# power_breakout.net
KiCad netlist of a schematic drawn in EAGLE
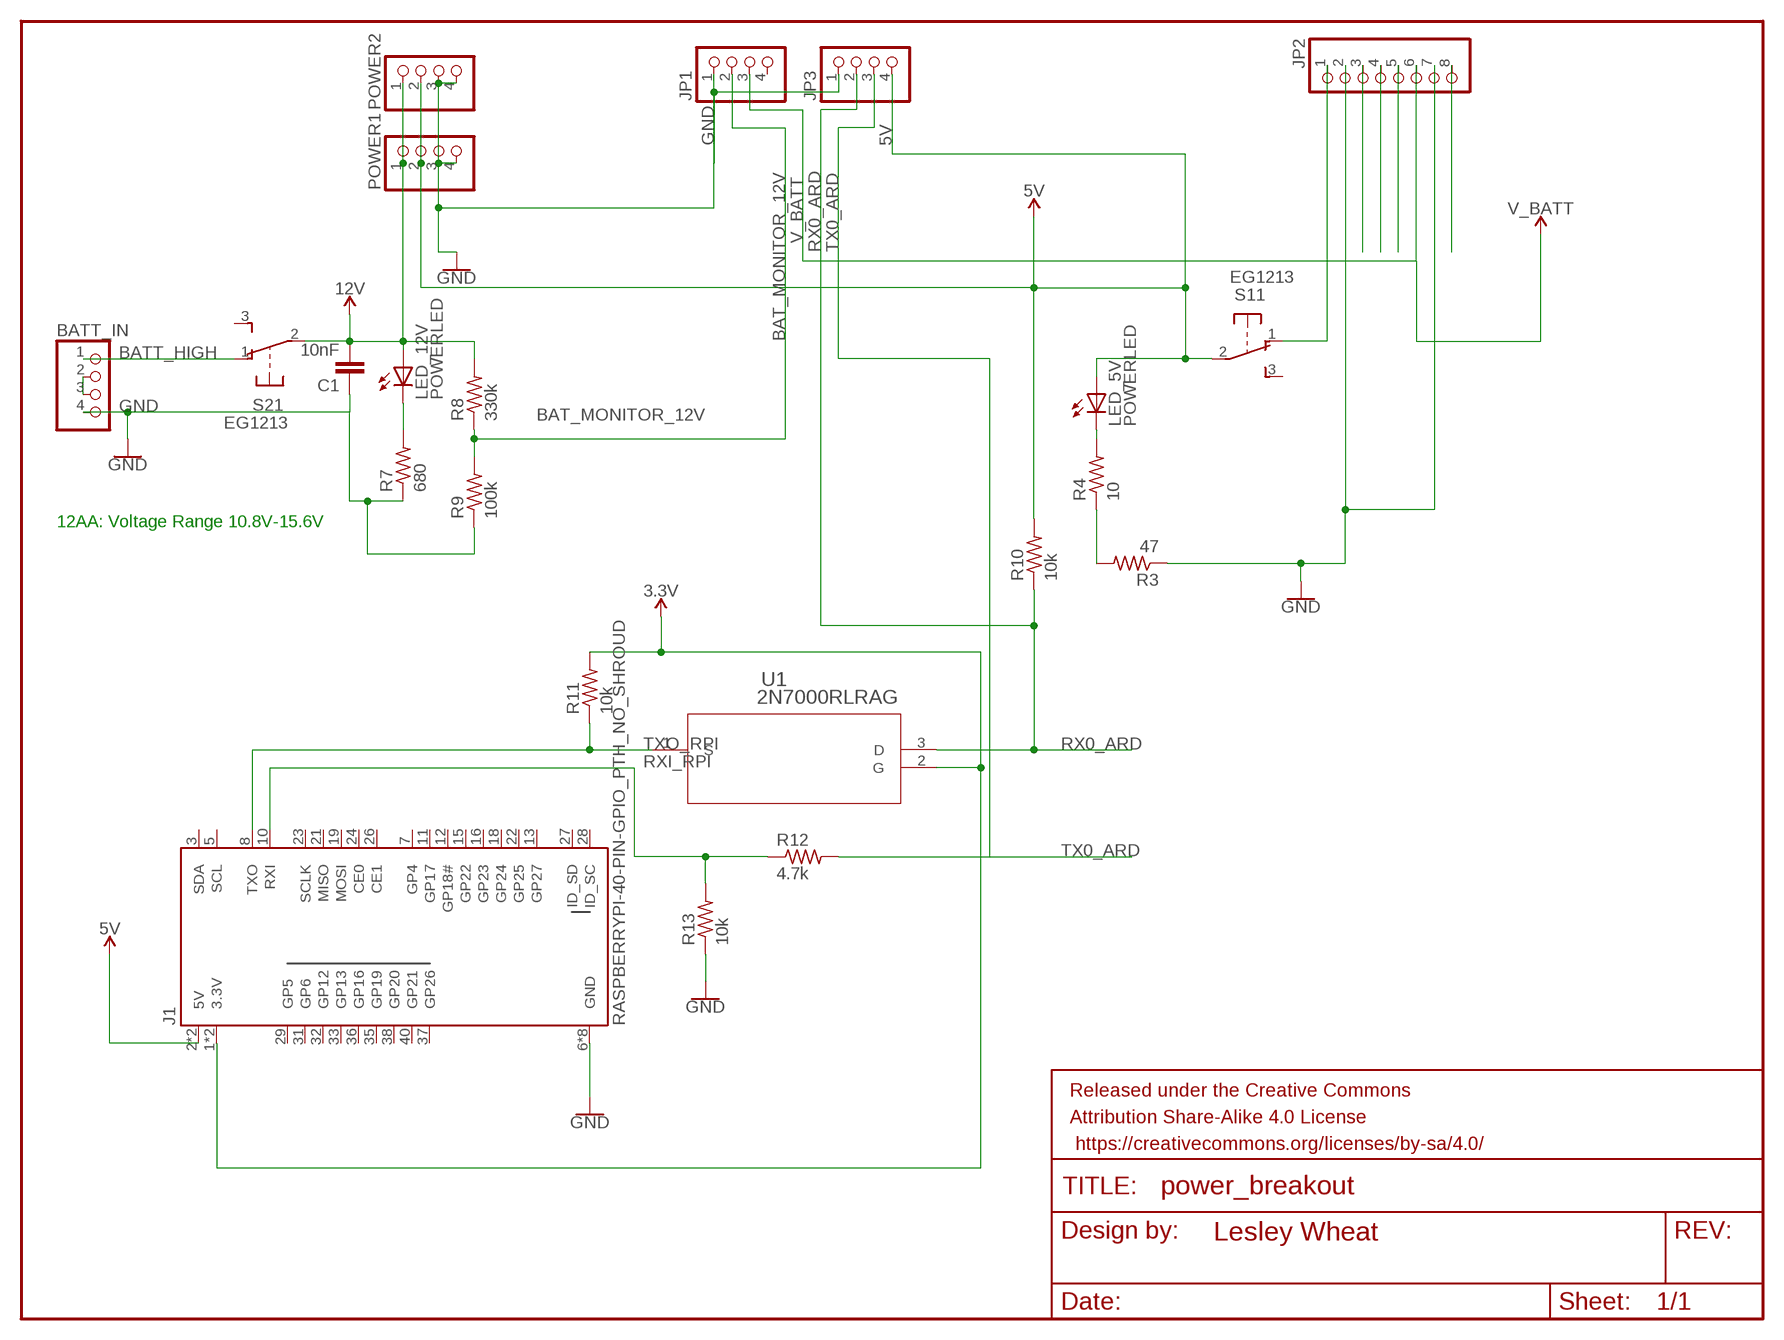
[diagram p0: schematic, sheet 1]

(export (version "E")
  (design (tool "Eeschema 10.0.6"))
  (components
    (comp (ref "BATT_IN")
      (value "PINHD-1X4")
      (footprint "eagle-import:1X04")
      (libsource (lib "eagle-import") (part "PINHD-1X4"))
    )
    (comp (ref "C1")
      (value "10nF")
      (footprint "eagle-import:CAP-PTH-10MM")
      (libsource (lib "eagle-import") (part "10NF-PTH-10MM-10000V-1-%"))
    )
    (comp (ref "FRAME1")
      (value "FRAME-LETTERNO_PACKAGE")
      (footprint "eagle-import:DUMMY")
      (fields (field (name "DESIGNER") "Lesley Wheat") (field (name "DESIGNER_1") "Lesley Wheat"))
      (libsource (lib "eagle-import") (part "FRAME-LETTERNO_PACKAGE"))
    )
    (comp (ref "J1")
      (value "RASPBERRYPI-40-PIN-GPIO_PTH_NO_SHROUD")
      (footprint "eagle-import:2X20")
      (libsource (lib "eagle-import") (part "RASPBERRYPI-40-PIN-GPIO_PTH_NO_SHROUD"))
    )
    (comp (ref "JP1")
      (value "PINHD-1X4")
      (footprint "eagle-import:1X04")
      (libsource (lib "eagle-import") (part "PINHD-1X4"))
    )
    (comp (ref "JP2")
      (value "PINHD-1X8")
      (footprint "eagle-import:1X08")
      (libsource (lib "eagle-import") (part "PINHD-1X8"))
    )
    (comp (ref "JP3")
      (value "PINHD-1X4")
      (footprint "eagle-import:1X04")
      (libsource (lib "eagle-import") (part "PINHD-1X4"))
    )
    (comp (ref "LED_5V")
      (value "POWERLED")
      (footprint "eagle-import:LED5MM")
      (libsource (lib "eagle-import") (part "LED5MM"))
    )
    (comp (ref "LED_12V")
      (value "POWERLED")
      (footprint "eagle-import:LED5MM")
      (libsource (lib "eagle-import") (part "LED5MM"))
    )
    (comp (ref "POWER1")
      (value "PINHD-1X4")
      (footprint "eagle-import:1X04")
      (libsource (lib "eagle-import") (part "PINHD-1X4"))
    )
    (comp (ref "POWER2")
      (value "PINHD-1X4")
      (footprint "eagle-import:1X04")
      (libsource (lib "eagle-import") (part "PINHD-1X4"))
    )
    (comp (ref "R3")
      (value "47")
      (footprint "eagle-import:0207_12")
      (libsource (lib "eagle-import") (part "R-US_0207/12"))
    )
    (comp (ref "R4")
      (value "10")
      (footprint "eagle-import:0207_12")
      (libsource (lib "eagle-import") (part "R-US_0207/12"))
    )
    (comp (ref "R7")
      (value "680")
      (footprint "eagle-import:0207_12")
      (libsource (lib "eagle-import") (part "R-US_0207/12"))
    )
    (comp (ref "R8")
      (value "330k")
      (footprint "eagle-import:0207_12")
      (libsource (lib "eagle-import") (part "R-US_0207/12"))
    )
    (comp (ref "R9")
      (value "100k")
      (footprint "eagle-import:0207_12")
      (libsource (lib "eagle-import") (part "R-US_0207/12"))
    )
    (comp (ref "R10")
      (value "10k")
      (footprint "eagle-import:0207_12")
      (libsource (lib "eagle-import") (part "R-US_0207/12"))
    )
    (comp (ref "R11")
      (value "10k")
      (footprint "eagle-import:0207_12")
      (libsource (lib "eagle-import") (part "R-US_0207/12"))
    )
    (comp (ref "R12")
      (value "4.7k")
      (footprint "eagle-import:0207_12")
      (libsource (lib "eagle-import") (part "R-US_0207/12"))
    )
    (comp (ref "R13")
      (value "10k")
      (footprint "eagle-import:0207_12")
      (libsource (lib "eagle-import") (part "R-US_0207/12"))
    )
    (comp (ref "S1")
      (value "EG1213")
      (footprint "eagle-import:EG1213")
      (libsource (lib "eagle-import") (part "EG1213"))
    )
    (comp (ref "S2")
      (value "EG1213")
      (footprint "eagle-import:EG1213")
      (libsource (lib "eagle-import") (part "EG1213"))
    )
    (comp (ref "U1")
      (value "2N7000RLRAG")
      (footprint "eagle-import:TO-92")
      (libsource (lib "eagle-import") (part "2N7000RLRAG"))
    )
  )
  (nets
    (net (code "1") (name "/BATT_HIGH") (class "Default")
      (node (ref "BATT_IN") (pin "1") (pinfunction "1_1") (pintype "passive"))
      (node (ref "S2") (pin "1") (pinfunction "O_1") (pintype "passive"))
    )
    (net (code "2") (name "/BAT_MONITOR_12V") (class "Default")
      (node (ref "JP1") (pin "2") (pinfunction "2_2") (pintype "passive"))
      (node (ref "R8") (pin "1") (pinfunction "1_1") (pintype "passive"))
      (node (ref "R9") (pin "2") (pinfunction "2_2") (pintype "passive"))
    )
    (net (code "3") (name "/RX0_ARD") (class "Default")
      (node (ref "JP3") (pin "2") (pinfunction "2_2") (pintype "passive"))
      (node (ref "R10") (pin "1") (pinfunction "1_1") (pintype "passive"))
      (node (ref "U1") (pin "3") (pinfunction "D_3") (pintype "passive"))
    )
    (net (code "4") (name "/RXI_RPI") (class "Default")
      (node (ref "J1") (pin "10") (pinfunction "RXI_10") (pintype "input"))
      (node (ref "R12") (pin "1") (pinfunction "1_1") (pintype "passive"))
      (node (ref "R13") (pin "2") (pinfunction "2_2") (pintype "passive"))
    )
    (net (code "5") (name "/TX0_ARD") (class "Default")
      (node (ref "JP3") (pin "3") (pinfunction "3_3") (pintype "passive"))
      (node (ref "R12") (pin "2") (pinfunction "2_2") (pintype "passive"))
    )
    (net (code "6") (name "/TXO_RPI") (class "Default")
      (node (ref "J1") (pin "8") (pinfunction "TXO_8") (pintype "output"))
      (node (ref "R11") (pin "1") (pinfunction "1_1") (pintype "passive"))
      (node (ref "U1") (pin "1") (pinfunction "S_1") (pintype "passive"))
    )
    (net (code "7") (name "3.3V") (class "Default")
      (node (ref "J1") (pin "1") (pinfunction "3.3V_1") (pintype "power_in"))
      (node (ref "J1") (pin "17") (pinfunction "3.3V_17") (pintype "power_in"))
      (node (ref "R11") (pin "2") (pinfunction "2_2") (pintype "passive"))
      (node (ref "U1") (pin "2") (pinfunction "G_2") (pintype "passive"))
    )
    (net (code "8") (name "5V") (class "Default")
      (node (ref "J1") (pin "2") (pinfunction "5V_2") (pintype "power_in"))
      (node (ref "J1") (pin "4") (pinfunction "5V_4") (pintype "power_in"))
      (node (ref "JP3") (pin "4") (pinfunction "4_4") (pintype "passive"))
      (node (ref "LED_5V") (pin "A") (pinfunction "A_A") (pintype "passive"))
      (node (ref "POWER1") (pin "2") (pinfunction "2_2") (pintype "passive"))
      (node (ref "POWER2") (pin "2") (pinfunction "2_2") (pintype "passive"))
      (node (ref "R10") (pin "2") (pinfunction "2_2") (pintype "passive"))
      (node (ref "S1") (pin "2") (pinfunction "P_2") (pintype "passive"))
    )
    (net (code "9") (name "12V") (class "Default")
      (node (ref "C1") (pin "2") (pinfunction "2_2") (pintype "passive"))
      (node (ref "LED_12V") (pin "A") (pinfunction "A_A") (pintype "passive"))
      (node (ref "POWER1") (pin "1") (pinfunction "1_1") (pintype "passive"))
      (node (ref "POWER2") (pin "1") (pinfunction "1_1") (pintype "passive"))
      (node (ref "R8") (pin "2") (pinfunction "2_2") (pintype "passive"))
      (node (ref "S2") (pin "2") (pinfunction "P_2") (pintype "passive"))
    )
    (net (code "10") (name "GND") (class "Default")
      (node (ref "BATT_IN") (pin "4") (pinfunction "4_4") (pintype "passive"))
      (node (ref "C1") (pin "1") (pinfunction "1_1") (pintype "passive"))
      (node (ref "J1") (pin "14") (pinfunction "GND_14") (pintype "power_in"))
      (node (ref "J1") (pin "20") (pinfunction "GND_20") (pintype "power_in"))
      (node (ref "J1") (pin "25") (pinfunction "GND_25") (pintype "power_in"))
      (node (ref "J1") (pin "30") (pinfunction "GND_30") (pintype "power_in"))
      (node (ref "J1") (pin "34") (pinfunction "GND_34") (pintype "power_in"))
      (node (ref "J1") (pin "39") (pinfunction "GND_39") (pintype "power_in"))
      (node (ref "J1") (pin "6") (pinfunction "GND_6") (pintype "power_in"))
      (node (ref "J1") (pin "9") (pinfunction "GND_9") (pintype "power_in"))
      (node (ref "JP1") (pin "1") (pinfunction "1_1") (pintype "passive"))
      (node (ref "JP2") (pin "2") (pinfunction "2_2") (pintype "passive"))
      (node (ref "JP2") (pin "7") (pinfunction "7_7") (pintype "passive"))
      (node (ref "JP3") (pin "1") (pinfunction "1_1") (pintype "passive"))
      (node (ref "POWER1") (pin "3") (pinfunction "3_3") (pintype "passive"))
      (node (ref "POWER1") (pin "4") (pinfunction "4_4") (pintype "passive"))
      (node (ref "POWER2") (pin "3") (pinfunction "3_3") (pintype "passive"))
      (node (ref "POWER2") (pin "4") (pinfunction "4_4") (pintype "passive"))
      (node (ref "R13") (pin "1") (pinfunction "1_1") (pintype "passive"))
      (node (ref "R3") (pin "1") (pinfunction "1_1") (pintype "passive"))
      (node (ref "R7") (pin "1") (pinfunction "1_1") (pintype "passive"))
      (node (ref "R9") (pin "1") (pinfunction "1_1") (pintype "passive"))
    )
    (net (code "11") (name "Net-(BATT_IN-Pad2)") (class "Default")
      (node (ref "BATT_IN") (pin "2") (pinfunction "2_2") (pintype "passive"))
      (node (ref "BATT_IN") (pin "3") (pinfunction "3_3") (pintype "passive"))
    )
    (net (code "12") (name "Net-(LED_5V-C)") (class "Default")
      (node (ref "LED_5V") (pin "K") (pinfunction "C_K") (pintype "passive"))
      (node (ref "R4") (pin "2") (pinfunction "2_2") (pintype "passive"))
    )
    (net (code "13") (name "Net-(LED_12V-C)") (class "Default")
      (node (ref "LED_12V") (pin "K") (pinfunction "C_K") (pintype "passive"))
      (node (ref "R7") (pin "2") (pinfunction "2_2") (pintype "passive"))
    )
    (net (code "14") (name "Net-(R3-Pad2)") (class "Default")
      (node (ref "R3") (pin "2") (pinfunction "2_2") (pintype "passive"))
      (node (ref "R4") (pin "1") (pinfunction "1_1") (pintype "passive"))
    )
    (net (code "15") (name "Net-(S1A-O)") (class "Default")
      (node (ref "JP2") (pin "1") (pinfunction "1_1") (pintype "passive"))
      (node (ref "S1") (pin "1") (pinfunction "O_1") (pintype "passive"))
    )
    (net (code "16") (name "V_BATT") (class "Default")
      (node (ref "JP1") (pin "3") (pinfunction "3_3") (pintype "passive"))
      (node (ref "JP2") (pin "6") (pinfunction "6_6") (pintype "passive"))
    )
    (net (code "17") (name "unconnected-(J1-CE0-Pad24)") (class "Default")
      (node (ref "J1") (pin "24") (pinfunction "CE0_24") (pintype "output"))
    )
    (net (code "18") (name "unconnected-(J1-CE1-Pad26)") (class "Default")
      (node (ref "J1") (pin "26") (pinfunction "CE1_26") (pintype "output"))
    )
    (net (code "19") (name "unconnected-(J1-GP4-Pad7)") (class "Default")
      (node (ref "J1") (pin "7") (pinfunction "GP4_7") (pintype "bidirectional"))
    )
    (net (code "20") (name "unconnected-(J1-GP5-Pad29)") (class "Default")
      (node (ref "J1") (pin "29") (pinfunction "GP5_29") (pintype "bidirectional"))
    )
    (net (code "21") (name "unconnected-(J1-GP6-Pad31)") (class "Default")
      (node (ref "J1") (pin "31") (pinfunction "GP6_31") (pintype "bidirectional"))
    )
    (net (code "22") (name "unconnected-(J1-GP12-Pad32)") (class "Default")
      (node (ref "J1") (pin "32") (pinfunction "GP12_32") (pintype "bidirectional"))
    )
    (net (code "23") (name "unconnected-(J1-GP13-Pad33)") (class "Default")
      (node (ref "J1") (pin "33") (pinfunction "GP13_33") (pintype "bidirectional"))
    )
    (net (code "24") (name "unconnected-(J1-GP16-Pad36)") (class "Default")
      (node (ref "J1") (pin "36") (pinfunction "GP16_36") (pintype "bidirectional"))
    )
    (net (code "25") (name "unconnected-(J1-GP17-Pad11)") (class "Default")
      (node (ref "J1") (pin "11") (pinfunction "GP17_11") (pintype "bidirectional"))
    )
    (net (code "26") (name "unconnected-(J1-GP18#-Pad12)") (class "Default")
      (node (ref "J1") (pin "12") (pinfunction "GP18#_12") (pintype "bidirectional"))
    )
    (net (code "27") (name "unconnected-(J1-GP19-Pad35)") (class "Default")
      (node (ref "J1") (pin "35") (pinfunction "GP19_35") (pintype "bidirectional"))
    )
    (net (code "28") (name "unconnected-(J1-GP20-Pad38)") (class "Default")
      (node (ref "J1") (pin "38") (pinfunction "GP20_38") (pintype "bidirectional"))
    )
    (net (code "29") (name "unconnected-(J1-GP21-Pad40)") (class "Default")
      (node (ref "J1") (pin "40") (pinfunction "GP21_40") (pintype "bidirectional"))
    )
    (net (code "30") (name "unconnected-(J1-GP22-Pad15)") (class "Default")
      (node (ref "J1") (pin "15") (pinfunction "GP22_15") (pintype "bidirectional"))
    )
    (net (code "31") (name "unconnected-(J1-GP23-Pad16)") (class "Default")
      (node (ref "J1") (pin "16") (pinfunction "GP23_16") (pintype "bidirectional"))
    )
    (net (code "32") (name "unconnected-(J1-GP24-Pad18)") (class "Default")
      (node (ref "J1") (pin "18") (pinfunction "GP24_18") (pintype "bidirectional"))
    )
    (net (code "33") (name "unconnected-(J1-GP25-Pad22)") (class "Default")
      (node (ref "J1") (pin "22") (pinfunction "GP25_22") (pintype "bidirectional"))
    )
    (net (code "34") (name "unconnected-(J1-GP26-Pad37)") (class "Default")
      (node (ref "J1") (pin "37") (pinfunction "GP26_37") (pintype "bidirectional"))
    )
    (net (code "35") (name "unconnected-(J1-GP27-Pad13)") (class "Default")
      (node (ref "J1") (pin "13") (pinfunction "GP27_13") (pintype "bidirectional"))
    )
    (net (code "36") (name "unconnected-(J1-ID_SC-Pad28)") (class "Default")
      (node (ref "J1") (pin "28") (pinfunction "ID_SC_28") (pintype "bidirectional"))
    )
    (net (code "37") (name "unconnected-(J1-ID_SD-Pad27)") (class "Default")
      (node (ref "J1") (pin "27") (pinfunction "ID_SD_27") (pintype "bidirectional"))
    )
    (net (code "38") (name "unconnected-(J1-MISO-Pad21)") (class "Default")
      (node (ref "J1") (pin "21") (pinfunction "MISO_21") (pintype "input"))
    )
    (net (code "39") (name "unconnected-(J1-MOSI-Pad19)") (class "Default")
      (node (ref "J1") (pin "19") (pinfunction "MOSI_19") (pintype "output"))
    )
    (net (code "40") (name "unconnected-(J1-SCL-Pad5)") (class "Default")
      (node (ref "J1") (pin "5") (pinfunction "SCL_5") (pintype "bidirectional"))
    )
    (net (code "41") (name "unconnected-(J1-SCLK-Pad23)") (class "Default")
      (node (ref "J1") (pin "23") (pinfunction "SCLK_23") (pintype "output"))
    )
    (net (code "42") (name "unconnected-(J1-SDA-Pad3)") (class "Default")
      (node (ref "J1") (pin "3") (pinfunction "SDA_3") (pintype "bidirectional"))
    )
    (net (code "43") (name "unconnected-(JP1-Pad4)") (class "Default")
      (node (ref "JP1") (pin "4") (pinfunction "4_4") (pintype "passive"))
    )
    (net (code "44") (name "unconnected-(JP2-Pad3)") (class "Default")
      (node (ref "JP2") (pin "3") (pinfunction "3_3") (pintype "passive"))
    )
    (net (code "45") (name "unconnected-(JP2-Pad4)") (class "Default")
      (node (ref "JP2") (pin "4") (pinfunction "4_4") (pintype "passive"))
    )
    (net (code "46") (name "unconnected-(JP2-Pad5)") (class "Default")
      (node (ref "JP2") (pin "5") (pinfunction "5_5") (pintype "passive"))
    )
    (net (code "47") (name "unconnected-(JP2-Pad8)") (class "Default")
      (node (ref "JP2") (pin "8") (pinfunction "8_8") (pintype "passive"))
    )
    (net (code "48") (name "unconnected-(S1A-S-Pad3)") (class "Default")
      (node (ref "S1") (pin "3") (pinfunction "S_3") (pintype "passive"))
    )
    (net (code "49") (name "unconnected-(S2A-S-Pad3)") (class "Default")
      (node (ref "S2") (pin "3") (pinfunction "S_3") (pintype "passive"))
    )
  )
)
